# PLL_Counter.net
KiCad netlist of a schematic drawn in EAGLE
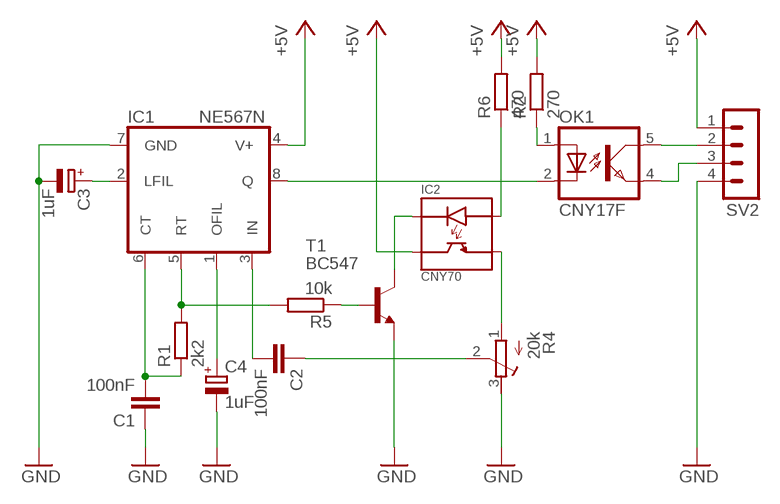
[diagram p0: schematic, sheet 1]

(export (version "E")
  (design (tool "Eeschema 10.0.6"))
  (components
    (comp (ref "C1")
      (value "100nF")
      (footprint "eagle-import:C025-025X050")
      (libsource (lib "eagle-import") (part "C-EU025-025X050"))
    )
    (comp (ref "C2")
      (value "100nF")
      (footprint "eagle-import:C025-025X050")
      (libsource (lib "eagle-import") (part "C-EU025-025X050"))
    )
    (comp (ref "C3")
      (value "1uF")
      (footprint "eagle-import:E2,5-5")
      (libsource (lib "eagle-import") (part "CPOL-EUE2.5-5"))
    )
    (comp (ref "C4")
      (value "1uF")
      (footprint "eagle-import:E2,5-5")
      (libsource (lib "eagle-import") (part "CPOL-EUE2.5-5"))
    )
    (comp (ref "IC1")
      (value "NE567N")
      (footprint "eagle-import:DIL08")
      (libsource (lib "eagle-import") (part "567NNE"))
    )
    (comp (ref "IC2")
      (value "CNY70")
      (footprint "eagle-import:CNY70")
      (libsource (lib "eagle-import") (part "CNY70"))
    )
    (comp (ref "OK1")
      (value "CNY17F")
      (footprint "eagle-import:DIL06")
      (fields (field (name "MF") "VISHAY/TELEFUNKEN") (field (name "MPN") "CNY17F-3"))
      (libsource (lib "eagle-import") (part "CNY17F"))
    )
    (comp (ref "R1")
      (value "2k2")
      (footprint "eagle-import:0204_7")
      (libsource (lib "eagle-import") (part "R-EU_0204/7"))
    )
    (comp (ref "R2")
      (value "270")
      (footprint "eagle-import:0204_7")
      (libsource (lib "eagle-import") (part "R-EU_0204/7"))
    )
    (comp (ref "R4")
      (value "20k")
      (footprint "eagle-import:RTRIM64X")
      (libsource (lib "eagle-import") (part "R-TRIMM64X"))
    )
    (comp (ref "R5")
      (value "10k")
      (footprint "eagle-import:0204_7")
      (libsource (lib "eagle-import") (part "R-EU_0204/7"))
    )
    (comp (ref "R6")
      (value "470")
      (footprint "eagle-import:0204_7")
      (libsource (lib "eagle-import") (part "R-EU_0204/7"))
    )
    (comp (ref "SV2")
      (value "MA04-1")
      (footprint "eagle-import:MA04-1")
      (libsource (lib "eagle-import") (part "MA04-1"))
    )
    (comp (ref "T1")
      (value "BC547")
      (footprint "eagle-import:TO92")
      (libsource (lib "eagle-import") (part "BC547"))
    )
  )
  (nets
    (net (code "1") (name "+5V") (class "Default")
      (node (ref "IC1") (pin "4") (pinfunction "V+_4") (pintype "power_in"))
      (node (ref "IC2") (pin "DC") (pinfunction "DC_DC") (pintype "bidirectional"))
      (node (ref "R2") (pin "2") (pinfunction "2_2") (pintype "passive"))
      (node (ref "R6") (pin "2") (pinfunction "2_2") (pintype "passive"))
      (node (ref "SV2") (pin "1") (pinfunction "1_1") (pintype "passive"))
    )
    (net (code "2") (name "GND") (class "Default")
      (node (ref "C1") (pin "1") (pinfunction "1_1") (pintype "passive"))
      (node (ref "C3") (pin "-") (pinfunction "-_-") (pintype "passive"))
      (node (ref "C4") (pin "-") (pinfunction "-_-") (pintype "passive"))
      (node (ref "IC1") (pin "7") (pinfunction "GND_7") (pintype "power_in"))
      (node (ref "R4") (pin "3") (pinfunction "E_3") (pintype "passive"))
      (node (ref "SV2") (pin "4") (pinfunction "4_4") (pintype "passive"))
      (node (ref "T1") (pin "1") (pinfunction "E_1") (pintype "passive"))
    )
    (net (code "3") (name "Net-(IC1-CT)") (class "Default")
      (node (ref "C1") (pin "2") (pinfunction "2_2") (pintype "passive"))
      (node (ref "IC1") (pin "6") (pinfunction "CT_6") (pintype "passive"))
      (node (ref "R1") (pin "1") (pinfunction "1_1") (pintype "passive"))
    )
    (net (code "4") (name "Net-(IC1-IN)") (class "Default")
      (node (ref "C2") (pin "2") (pinfunction "2_2") (pintype "passive"))
      (node (ref "IC1") (pin "3") (pinfunction "IN_3") (pintype "input"))
    )
    (net (code "5") (name "Net-(IC1-LFIL)") (class "Default")
      (node (ref "C3") (pin "+") (pinfunction "+_+") (pintype "passive"))
      (node (ref "IC1") (pin "2") (pinfunction "LFIL_2") (pintype "passive"))
    )
    (net (code "6") (name "Net-(IC1-OFIL)") (class "Default")
      (node (ref "C4") (pin "+") (pinfunction "+_+") (pintype "passive"))
      (node (ref "IC1") (pin "1") (pinfunction "OFIL_1") (pintype "output"))
    )
    (net (code "7") (name "Net-(IC1-Q)") (class "Default")
      (node (ref "IC1") (pin "8") (pinfunction "Q_8") (pintype "output"))
      (node (ref "OK1") (pin "2") (pinfunction "C_2") (pintype "passive"))
    )
    (net (code "8") (name "Net-(IC1-RT)") (class "Default")
      (node (ref "IC1") (pin "5") (pinfunction "RT_5") (pintype "passive"))
      (node (ref "R1") (pin "2") (pinfunction "2_2") (pintype "passive"))
      (node (ref "R5") (pin "2") (pinfunction "2_2") (pintype "passive"))
    )
    (net (code "9") (name "Net-(IC2-PadEA)") (class "Default")
      (node (ref "IC2") (pin "EA") (pinfunction "EA_EA") (pintype "bidirectional"))
      (node (ref "R6") (pin "1") (pinfunction "1_1") (pintype "passive"))
    )
    (net (code "10") (name "Net-(OK1-A)") (class "Default")
      (node (ref "OK1") (pin "1") (pinfunction "A_1") (pintype "passive"))
      (node (ref "R2") (pin "1") (pinfunction "1_1") (pintype "passive"))
    )
    (net (code "11") (name "Net-(OK1-COL)") (class "Default")
      (node (ref "OK1") (pin "5") (pinfunction "COL_5") (pintype "passive"))
      (node (ref "SV2") (pin "2") (pinfunction "2_2") (pintype "passive"))
    )
    (net (code "12") (name "Net-(OK1-EMIT)") (class "Default")
      (node (ref "OK1") (pin "4") (pinfunction "EMIT_4") (pintype "passive"))
      (node (ref "SV2") (pin "3") (pinfunction "3_3") (pintype "passive"))
    )
    (net (code "13") (name "Net-(R4-A)") (class "Default")
      (node (ref "IC2") (pin "DE") (pinfunction "DE_DE") (pintype "bidirectional"))
      (node (ref "R4") (pin "1") (pinfunction "A_1") (pintype "passive"))
    )
    (net (code "14") (name "Net-(R4-S)") (class "Default")
      (node (ref "C2") (pin "1") (pinfunction "1_1") (pintype "passive"))
      (node (ref "R4") (pin "2") (pinfunction "S_2") (pintype "passive"))
    )
    (net (code "15") (name "Net-(T1-B)") (class "Default")
      (node (ref "R5") (pin "1") (pinfunction "1_1") (pintype "passive"))
      (node (ref "T1") (pin "2") (pinfunction "B_2") (pintype "passive"))
    )
    (net (code "16") (name "Net-(T1-C)") (class "Default")
      (node (ref "IC2") (pin "EK") (pinfunction "EK_EK") (pintype "bidirectional"))
      (node (ref "T1") (pin "3") (pinfunction "C_3") (pintype "passive"))
    )
  )
)
